# SWD_PROGRAMMER_minimal.net
KiCad netlist of a schematic drawn in EAGLE
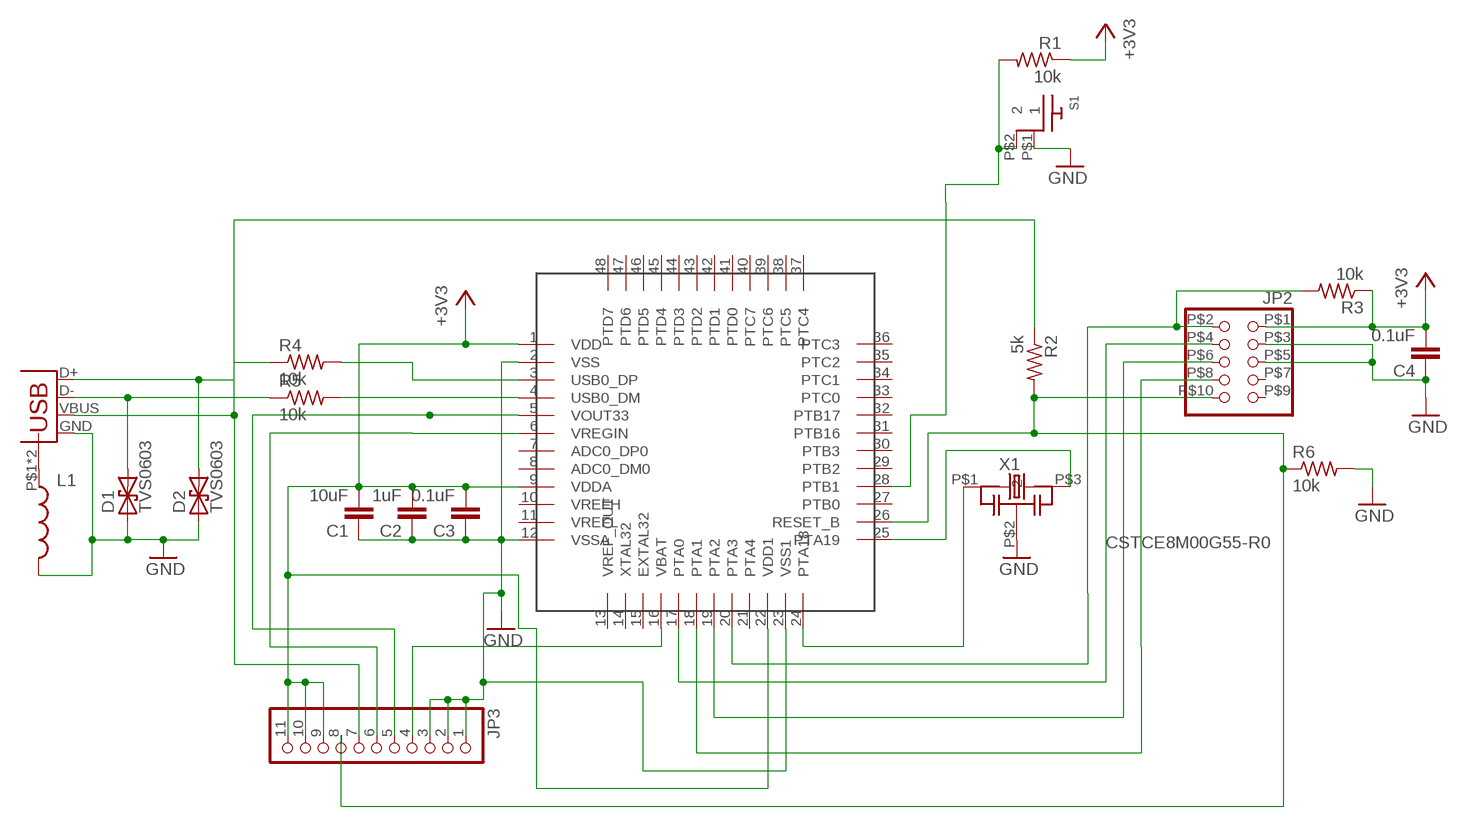
[diagram p0: schematic, sheet 1]

(export (version "E")
  (design (tool "Eeschema 10.0.6"))
  (components
    (comp (ref "C1")
      (value "10uF")
      (footprint "eagle-import:C0805")
      (libsource (lib "eagle-import") (part "RF-C0805"))
    )
    (comp (ref "C2")
      (value "1uF")
      (footprint "eagle-import:C0805")
      (libsource (lib "eagle-import") (part "RF-C0805"))
    )
    (comp (ref "C3")
      (value "0.1uF")
      (footprint "eagle-import:C0805")
      (libsource (lib "eagle-import") (part "RF-C0805"))
    )
    (comp (ref "C4")
      (value "0.1uF")
      (footprint "eagle-import:C0805")
      (libsource (lib "eagle-import") (part "RF-C0805"))
    )
    (comp (ref "D1")
      (value "TVS0603")
      (footprint "eagle-import:0603-RES")
      (libsource (lib "eagle-import") (part "TVS0603"))
    )
    (comp (ref "D2")
      (value "TVS0603")
      (footprint "eagle-import:0603-RES")
      (libsource (lib "eagle-import") (part "TVS0603"))
    )
    (comp (ref "J1")
      (value "USB_B")
      (footprint "eagle-import:USB-B-PTH-VERTICAL")
      (libsource (lib "eagle-import") (part "USB_B"))
    )
    (comp (ref "JP2")
      (value "PINHD-2X5SMALL")
      (footprint "eagle-import:2X5HDR")
      (libsource (lib "eagle-import") (part "PINHD-2X5SMALL"))
    )
    (comp (ref "JP3")
      (value "PINHD-1X11")
      (footprint "eagle-import:1X11")
      (libsource (lib "eagle-import") (part "PINHD-1X11"))
    )
    (comp (ref "L1")
      (value "INDUCTOR0603")
      (footprint "eagle-import:0603")
      (libsource (lib "eagle-import") (part "INDUCTOR0603"))
    )
    (comp (ref "R1")
      (value "10k")
      (footprint "eagle-import:RF-C0805")
      (libsource (lib "eagle-import") (part "RF-R0805"))
    )
    (comp (ref "R2")
      (value "5k")
      (footprint "eagle-import:RF-C0805")
      (libsource (lib "eagle-import") (part "RF-R0805"))
    )
    (comp (ref "R3")
      (value "10k")
      (footprint "eagle-import:RF-C0805")
      (libsource (lib "eagle-import") (part "RF-R0805"))
    )
    (comp (ref "R4")
      (value "10k")
      (footprint "eagle-import:RF-C0805")
      (libsource (lib "eagle-import") (part "RF-R0805"))
    )
    (comp (ref "R5")
      (value "10k")
      (footprint "eagle-import:RF-C0805")
      (libsource (lib "eagle-import") (part "RF-R0805"))
    )
    (comp (ref "R6")
      (value "10k")
      (footprint "eagle-import:RF-C0805")
      (libsource (lib "eagle-import") (part "RF-R0805"))
    )
    (comp (ref "S1")
      (value "RA_BUTTON")
      (footprint "eagle-import:RA_BUTTON")
      (libsource (lib "eagle-import") (part "RA_BUTTON"))
    )
    (comp (ref "U$1")
      (value "KL20_48")
      (footprint "eagle-import:LQFP-48")
      (libsource (lib "eagle-import") (part "KL20_48"))
    )
    (comp (ref "X1")
      (value "CSTCE8M00G55-R0")
      (footprint "eagle-import:CSTCE_G_A")
      (libsource (lib "eagle-import") (part "CSTCE8M00G55-R0"))
    )
  )
  (nets
    (net (code "1") (name "+3V3") (class "Default")
      (node (ref "C1") (pin "2") (pinfunction "2_2") (pintype "passive"))
      (node (ref "C2") (pin "2") (pinfunction "2_2") (pintype "passive"))
      (node (ref "C3") (pin "2") (pinfunction "2_2") (pintype "passive"))
      (node (ref "C4") (pin "2") (pinfunction "2_2") (pintype "passive"))
      (node (ref "JP2") (pin "P$1") (pinfunction "1_P$1") (pintype "passive"))
      (node (ref "JP3") (pin "10") (pinfunction "10_10") (pintype "passive"))
      (node (ref "JP3") (pin "11") (pinfunction "11_11") (pintype "passive"))
      (node (ref "JP3") (pin "9") (pinfunction "9_9") (pintype "passive"))
      (node (ref "R1") (pin "1") (pinfunction "1_1") (pintype "passive"))
      (node (ref "R3") (pin "1") (pinfunction "1_1") (pintype "passive"))
      (node (ref "U$1") (pin "1") (pinfunction "VDD_1") (pintype "bidirectional"))
      (node (ref "U$1") (pin "22") (pinfunction "VDD1_22") (pintype "bidirectional"))
      (node (ref "U$1") (pin "9") (pinfunction "VDDA_9") (pintype "bidirectional"))
    )
    (net (code "2") (name "GND") (class "Default")
      (node (ref "C1") (pin "1") (pinfunction "1_1") (pintype "passive"))
      (node (ref "C2") (pin "1") (pinfunction "1_1") (pintype "passive"))
      (node (ref "C3") (pin "1") (pinfunction "1_1") (pintype "passive"))
      (node (ref "C4") (pin "1") (pinfunction "1_1") (pintype "passive"))
      (node (ref "D1") (pin "1") (pinfunction "1_1") (pintype "passive"))
      (node (ref "D2") (pin "1") (pinfunction "1_1") (pintype "passive"))
      (node (ref "J1") (pin "GND") (pinfunction "GND_GND") (pintype "bidirectional"))
      (node (ref "JP2") (pin "P$3") (pinfunction "3_P$3") (pintype "passive"))
      (node (ref "JP2") (pin "P$5") (pinfunction "5_P$5") (pintype "passive"))
      (node (ref "JP3") (pin "1") (pinfunction "1_1") (pintype "passive"))
      (node (ref "JP3") (pin "2") (pinfunction "2_2") (pintype "passive"))
      (node (ref "JP3") (pin "3") (pinfunction "3_3") (pintype "passive"))
      (node (ref "L1") (pin "2") (pinfunction "2_2") (pintype "passive"))
      (node (ref "R6") (pin "2") (pinfunction "2_2") (pintype "passive"))
      (node (ref "S1") (pin "P$1") (pinfunction "1_P$1") (pintype "input"))
      (node (ref "U$1") (pin "12") (pinfunction "VSSA_12") (pintype "bidirectional"))
      (node (ref "U$1") (pin "2") (pinfunction "VSS_2") (pintype "bidirectional"))
      (node (ref "U$1") (pin "23") (pinfunction "VSS1_23") (pintype "bidirectional"))
      (node (ref "X1") (pin "P$2") (pinfunction "2_P$2") (pintype "passive"))
    )
    (net (code "3") (name "Net-(D1-Pad2)") (class "Default")
      (node (ref "D1") (pin "2") (pinfunction "2_2") (pintype "passive"))
      (node (ref "J1") (pin "D-") (pinfunction "D-_D-") (pintype "bidirectional"))
      (node (ref "R5") (pin "1") (pinfunction "1_1") (pintype "passive"))
    )
    (net (code "4") (name "Net-(D2-Pad2)") (class "Default")
      (node (ref "D2") (pin "2") (pinfunction "2_2") (pintype "passive"))
      (node (ref "J1") (pin "D+") (pinfunction "D+_D+") (pintype "bidirectional"))
      (node (ref "R4") (pin "1") (pinfunction "1_1") (pintype "passive"))
    )
    (net (code "5") (name "Net-(J1-PadVBUS)") (class "Default")
      (node (ref "J1") (pin "VBUS") (pinfunction "VBUS_VBUS") (pintype "bidirectional"))
      (node (ref "JP3") (pin "7") (pinfunction "7_7") (pintype "passive"))
      (node (ref "R2") (pin "1") (pinfunction "1_1") (pintype "passive"))
    )
    (net (code "6") (name "Net-(J1-SHIELD-PadP$1)") (class "Default")
      (node (ref "J1") (pin "P$1") (pinfunction "SHIELD_P$1") (pintype "bidirectional"))
      (node (ref "J1") (pin "P$2") (pinfunction "SHIELD_P$2") (pintype "bidirectional"))
      (node (ref "L1") (pin "1") (pinfunction "1_1") (pintype "passive"))
    )
    (net (code "7") (name "Net-(JP2-2)") (class "Default")
      (node (ref "JP2") (pin "P$2") (pinfunction "2_P$2") (pintype "passive"))
      (node (ref "R3") (pin "2") (pinfunction "2_2") (pintype "passive"))
      (node (ref "U$1") (pin "20") (pinfunction "PTA3_20") (pintype "bidirectional"))
    )
    (net (code "8") (name "Net-(JP2-4)") (class "Default")
      (node (ref "JP2") (pin "P$4") (pinfunction "4_P$4") (pintype "passive"))
      (node (ref "U$1") (pin "17") (pinfunction "PTA0_17") (pintype "bidirectional"))
    )
    (net (code "9") (name "Net-(JP2-6)") (class "Default")
      (node (ref "JP2") (pin "P$6") (pinfunction "6_P$6") (pintype "passive"))
      (node (ref "U$1") (pin "19") (pinfunction "PTA2_19") (pintype "bidirectional"))
    )
    (net (code "10") (name "Net-(JP2-8)") (class "Default")
      (node (ref "JP2") (pin "P$8") (pinfunction "8_P$8") (pintype "passive"))
      (node (ref "U$1") (pin "18") (pinfunction "PTA1_18") (pintype "bidirectional"))
    )
    (net (code "11") (name "Net-(JP2-10)") (class "Default")
      (node (ref "JP2") (pin "P$10") (pinfunction "10_P$10") (pintype "passive"))
      (node (ref "JP3") (pin "8") (pinfunction "8_8") (pintype "passive"))
      (node (ref "R2") (pin "2") (pinfunction "2_2") (pintype "passive"))
      (node (ref "R6") (pin "1") (pinfunction "1_1") (pintype "passive"))
      (node (ref "U$1") (pin "26") (pinfunction "RESET_B_26") (pintype "bidirectional"))
    )
    (net (code "12") (name "Net-(S1-2)") (class "Default")
      (node (ref "R1") (pin "2") (pinfunction "2_2") (pintype "passive"))
      (node (ref "S1") (pin "P$2") (pinfunction "2_P$2") (pintype "input"))
      (node (ref "U$1") (pin "28") (pinfunction "PTB1_28") (pintype "bidirectional"))
    )
    (net (code "13") (name "Net-(U$1-PTA18)") (class "Default")
      (node (ref "U$1") (pin "24") (pinfunction "PTA18_24") (pintype "bidirectional"))
      (node (ref "X1") (pin "P$1") (pinfunction "1_P$1") (pintype "passive"))
    )
    (net (code "14") (name "Net-(U$1-PTA19)") (class "Default")
      (node (ref "U$1") (pin "25") (pinfunction "PTA19_25") (pintype "bidirectional"))
      (node (ref "X1") (pin "P$3") (pinfunction "3_P$3") (pintype "passive"))
    )
    (net (code "15") (name "Net-(U$1-USB0_DM)") (class "Default")
      (node (ref "R5") (pin "2") (pinfunction "2_2") (pintype "passive"))
      (node (ref "U$1") (pin "4") (pinfunction "USB0_DM_4") (pintype "bidirectional"))
    )
    (net (code "16") (name "Net-(U$1-USB0_DP)") (class "Default")
      (node (ref "R4") (pin "2") (pinfunction "2_2") (pintype "passive"))
      (node (ref "U$1") (pin "3") (pinfunction "USB0_DP_3") (pintype "bidirectional"))
    )
    (net (code "17") (name "Net-(U$1-VBAT)") (class "Default")
      (node (ref "JP3") (pin "4") (pinfunction "4_4") (pintype "passive"))
      (node (ref "U$1") (pin "16") (pinfunction "VBAT_16") (pintype "bidirectional"))
    )
    (net (code "18") (name "Net-(U$1-VOUT33)") (class "Default")
      (node (ref "JP3") (pin "5") (pinfunction "5_5") (pintype "passive"))
      (node (ref "U$1") (pin "5") (pinfunction "VOUT33_5") (pintype "bidirectional"))
    )
    (net (code "19") (name "Net-(U$1-VREGIN)") (class "Default")
      (node (ref "JP3") (pin "6") (pinfunction "6_6") (pintype "passive"))
      (node (ref "U$1") (pin "6") (pinfunction "VREGIN_6") (pintype "bidirectional"))
    )
    (net (code "20") (name "unconnected-(JP2-7-PadP$7)") (class "Default")
      (node (ref "JP2") (pin "P$7") (pinfunction "7_P$7") (pintype "passive"))
    )
    (net (code "21") (name "unconnected-(JP2-9-PadP$9)") (class "Default")
      (node (ref "JP2") (pin "P$9") (pinfunction "9_P$9") (pintype "passive"))
    )
    (net (code "22") (name "unconnected-(U$1-ADC0_DM0-Pad8)") (class "Default")
      (node (ref "U$1") (pin "8") (pinfunction "ADC0_DM0_8") (pintype "bidirectional"))
    )
    (net (code "23") (name "unconnected-(U$1-ADC0_DP0-Pad7)") (class "Default")
      (node (ref "U$1") (pin "7") (pinfunction "ADC0_DP0_7") (pintype "bidirectional"))
    )
    (net (code "24") (name "unconnected-(U$1-EXTAL32-Pad15)") (class "Default")
      (node (ref "U$1") (pin "15") (pinfunction "EXTAL32_15") (pintype "bidirectional"))
    )
    (net (code "25") (name "unconnected-(U$1-PTA4-Pad21)") (class "Default")
      (node (ref "U$1") (pin "21") (pinfunction "PTA4_21") (pintype "bidirectional"))
    )
    (net (code "26") (name "unconnected-(U$1-PTB0-Pad27)") (class "Default")
      (node (ref "U$1") (pin "27") (pinfunction "PTB0_27") (pintype "bidirectional"))
    )
    (net (code "27") (name "unconnected-(U$1-PTB2-Pad29)") (class "Default")
      (node (ref "U$1") (pin "29") (pinfunction "PTB2_29") (pintype "bidirectional"))
    )
    (net (code "28") (name "unconnected-(U$1-PTB3-Pad30)") (class "Default")
      (node (ref "U$1") (pin "30") (pinfunction "PTB3_30") (pintype "bidirectional"))
    )
    (net (code "29") (name "unconnected-(U$1-PTB16-Pad31)") (class "Default")
      (node (ref "U$1") (pin "31") (pinfunction "PTB16_31") (pintype "bidirectional"))
    )
    (net (code "30") (name "unconnected-(U$1-PTB17-Pad32)") (class "Default")
      (node (ref "U$1") (pin "32") (pinfunction "PTB17_32") (pintype "bidirectional"))
    )
    (net (code "31") (name "unconnected-(U$1-PTC0-Pad33)") (class "Default")
      (node (ref "U$1") (pin "33") (pinfunction "PTC0_33") (pintype "bidirectional"))
    )
    (net (code "32") (name "unconnected-(U$1-PTC1-Pad34)") (class "Default")
      (node (ref "U$1") (pin "34") (pinfunction "PTC1_34") (pintype "bidirectional"))
    )
    (net (code "33") (name "unconnected-(U$1-PTC2-Pad35)") (class "Default")
      (node (ref "U$1") (pin "35") (pinfunction "PTC2_35") (pintype "bidirectional"))
    )
    (net (code "34") (name "unconnected-(U$1-PTC3-Pad36)") (class "Default")
      (node (ref "U$1") (pin "36") (pinfunction "PTC3_36") (pintype "bidirectional"))
    )
    (net (code "35") (name "unconnected-(U$1-PTC4-Pad37)") (class "Default")
      (node (ref "U$1") (pin "37") (pinfunction "PTC4_37") (pintype "bidirectional"))
    )
    (net (code "36") (name "unconnected-(U$1-PTC5-Pad38)") (class "Default")
      (node (ref "U$1") (pin "38") (pinfunction "PTC5_38") (pintype "bidirectional"))
    )
    (net (code "37") (name "unconnected-(U$1-PTC6-Pad39)") (class "Default")
      (node (ref "U$1") (pin "39") (pinfunction "PTC6_39") (pintype "bidirectional"))
    )
    (net (code "38") (name "unconnected-(U$1-PTC7-Pad40)") (class "Default")
      (node (ref "U$1") (pin "40") (pinfunction "PTC7_40") (pintype "bidirectional"))
    )
    (net (code "39") (name "unconnected-(U$1-PTD0-Pad41)") (class "Default")
      (node (ref "U$1") (pin "41") (pinfunction "PTD0_41") (pintype "bidirectional"))
    )
    (net (code "40") (name "unconnected-(U$1-PTD1-Pad42)") (class "Default")
      (node (ref "U$1") (pin "42") (pinfunction "PTD1_42") (pintype "bidirectional"))
    )
    (net (code "41") (name "unconnected-(U$1-PTD2-Pad43)") (class "Default")
      (node (ref "U$1") (pin "43") (pinfunction "PTD2_43") (pintype "bidirectional"))
    )
    (net (code "42") (name "unconnected-(U$1-PTD3-Pad44)") (class "Default")
      (node (ref "U$1") (pin "44") (pinfunction "PTD3_44") (pintype "bidirectional"))
    )
    (net (code "43") (name "unconnected-(U$1-PTD4-Pad45)") (class "Default")
      (node (ref "U$1") (pin "45") (pinfunction "PTD4_45") (pintype "bidirectional"))
    )
    (net (code "44") (name "unconnected-(U$1-PTD5-Pad46)") (class "Default")
      (node (ref "U$1") (pin "46") (pinfunction "PTD5_46") (pintype "bidirectional"))
    )
    (net (code "45") (name "unconnected-(U$1-PTD6-Pad47)") (class "Default")
      (node (ref "U$1") (pin "47") (pinfunction "PTD6_47") (pintype "bidirectional"))
    )
    (net (code "46") (name "unconnected-(U$1-PTD7-Pad48)") (class "Default")
      (node (ref "U$1") (pin "48") (pinfunction "PTD7_48") (pintype "bidirectional"))
    )
    (net (code "47") (name "unconnected-(U$1-VREFH-Pad10)") (class "Default")
      (node (ref "U$1") (pin "10") (pinfunction "VREFH_10") (pintype "bidirectional"))
    )
    (net (code "48") (name "unconnected-(U$1-VREFL-Pad11)") (class "Default")
      (node (ref "U$1") (pin "11") (pinfunction "VREFL_11") (pintype "bidirectional"))
    )
    (net (code "49") (name "unconnected-(U$1-VREF_OUT-Pad13)") (class "Default")
      (node (ref "U$1") (pin "13") (pinfunction "VREF_OUT_13") (pintype "bidirectional"))
    )
    (net (code "50") (name "unconnected-(U$1-XTAL32-Pad14)") (class "Default")
      (node (ref "U$1") (pin "14") (pinfunction "XTAL32_14") (pintype "bidirectional"))
    )
  )
)
